# Board_scheme.net
KiCad netlist of a schematic drawn in EasyEDA
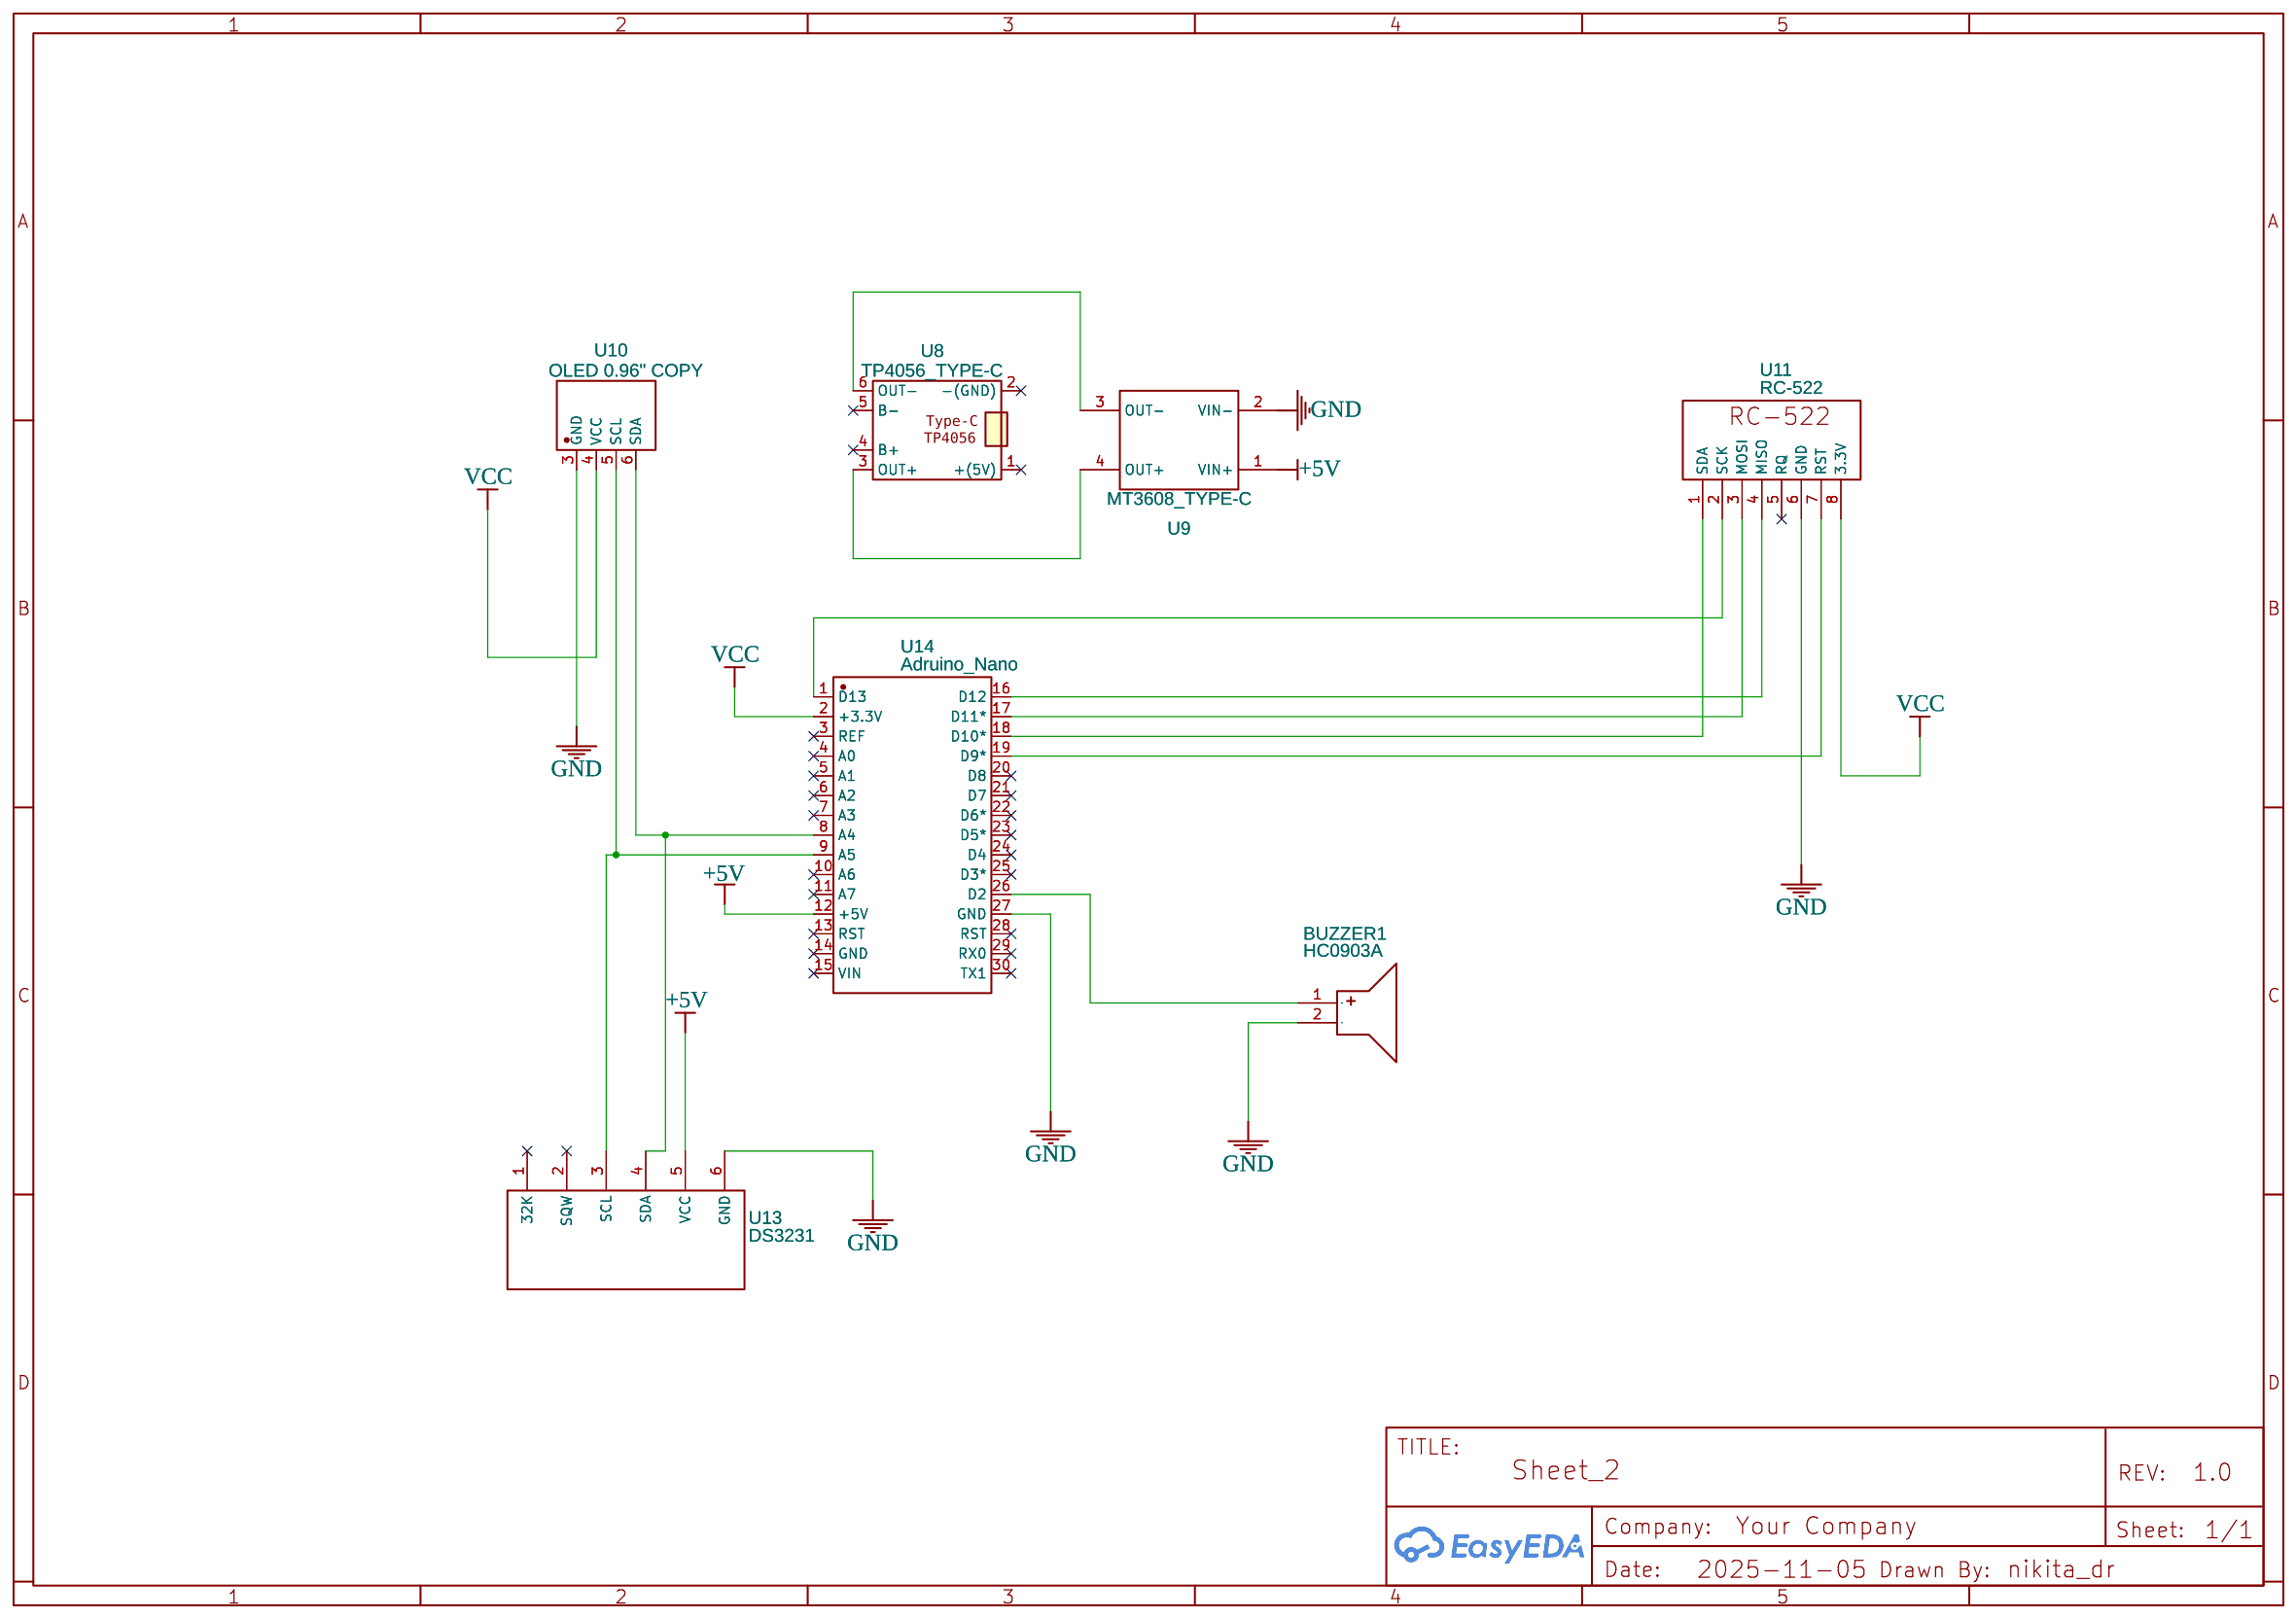
[diagram p0: schematic sheet]

(export (version "E")
  (design (tool "Eeschema 10.0.6"))
  (components
    (comp (ref "BUZZER1")
      (value "HC0903A")
      (fields (field (name "Manufacturer") "INGHAi"))
      (libsource (lib "") (part "HC0903A"))
    )
    (comp (ref "U8") (value "TP4056_TYPE-C") (libsource (lib "") (part "TP4056_TYPE-C")))
    (comp (ref "U9")
      (value "MT3608_TYPE-C")
      (fields (field (name "Manufacturer") "Simple Robot Store"))
      (libsource (lib "") (part "MT3608_TYPE-C"))
    )
    (comp (ref "U10")
      (value "OLED 0.96\" COPY")
      (fields
        (field (name "Manufacturer Part") "ZJY096S0700BG01蓝色")
        (field (name "Manufacturer") "AZDelivery")
      )
      (libsource (lib "") (part "OLED 0.96{dblquote} COPY"))
    )
    (comp (ref "U11") (value "RC-522") (libsource (lib "") (part "RC-522")))
    (comp (ref "U13")
      (value "DS3231")
      (fields (field (name "Manufacturer Part") "New SchematicLib"))
      (libsource (lib "") (part "DS3231"))
    )
    (comp (ref "U14") (value "Adruino_Nano") (libsource (lib "") (part "Adruino_Nano")))
  )
  (nets
    (net (code "1") (name "+5V") (class "Default")
      (node (ref "U13") (pin "5") (pinfunction "VCC_5") (pintype "unspecified"))
      (node (ref "U14") (pin "12") (pinfunction "+5V_12") (pintype "unspecified"))
      (node (ref "U9") (pin "1") (pinfunction "VIN+_1") (pintype "unspecified"))
    )
    (net (code "2") (name "GND") (class "Default")
      (node (ref "BUZZER1") (pin "2") (pinfunction "-_2") (pintype "unspecified"))
      (node (ref "U10") (pin "3") (pinfunction "GND_3") (pintype "unspecified"))
      (node (ref "U11") (pin "6") (pinfunction "GND_6") (pintype "unspecified"))
      (node (ref "U13") (pin "6") (pinfunction "GND_6") (pintype "unspecified"))
      (node (ref "U14") (pin "27") (pinfunction "GND_27") (pintype "unspecified"))
      (node (ref "U9") (pin "2") (pinfunction "VIN-_2") (pintype "unspecified"))
    )
    (net (code "3") (name "Net-(BUZZER1-+)") (class "Default")
      (node (ref "BUZZER1") (pin "1") (pinfunction "+_1") (pintype "unspecified"))
      (node (ref "U14") (pin "26") (pinfunction "D2_26") (pintype "unspecified"))
    )
    (net (code "4") (name "Net-(U8-OUT+)") (class "Default")
      (node (ref "U8") (pin "3") (pinfunction "OUT+_3") (pintype "unspecified"))
      (node (ref "U9") (pin "4") (pinfunction "OUT+_4") (pintype "unspecified"))
    )
    (net (code "5") (name "Net-(U8-OUT-)") (class "Default")
      (node (ref "U8") (pin "6") (pinfunction "OUT-_6") (pintype "unspecified"))
      (node (ref "U9") (pin "3") (pinfunction "OUT-_3") (pintype "unspecified"))
    )
    (net (code "6") (name "Net-(U10-SCL)") (class "Default")
      (node (ref "U10") (pin "5") (pinfunction "SCL_5") (pintype "unspecified"))
      (node (ref "U13") (pin "3") (pinfunction "SCL_3") (pintype "unspecified"))
      (node (ref "U14") (pin "9") (pinfunction "A5_9") (pintype "unspecified"))
    )
    (net (code "7") (name "Net-(U10-SDA)") (class "Default")
      (node (ref "U10") (pin "6") (pinfunction "SDA_6") (pintype "unspecified"))
      (node (ref "U13") (pin "4") (pinfunction "SDA_4") (pintype "unspecified"))
      (node (ref "U14") (pin "8") (pinfunction "A4_8") (pintype "unspecified"))
    )
    (net (code "8") (name "Net-(U11-MISO)") (class "Default")
      (node (ref "U11") (pin "4") (pinfunction "MISO_4") (pintype "unspecified"))
      (node (ref "U14") (pin "16") (pinfunction "D12_16") (pintype "unspecified"))
    )
    (net (code "9") (name "Net-(U11-MOSI)") (class "Default")
      (node (ref "U11") (pin "3") (pinfunction "MOSI_3") (pintype "unspecified"))
      (node (ref "U14") (pin "17") (pinfunction "D11*_17") (pintype "unspecified"))
    )
    (net (code "10") (name "Net-(U11-RST)") (class "Default")
      (node (ref "U11") (pin "7") (pinfunction "RST_7") (pintype "unspecified"))
      (node (ref "U14") (pin "19") (pinfunction "D9*_19") (pintype "unspecified"))
    )
    (net (code "11") (name "Net-(U11-SCK)") (class "Default")
      (node (ref "U11") (pin "2") (pinfunction "SCK_2") (pintype "unspecified"))
      (node (ref "U14") (pin "1") (pinfunction "D13_1") (pintype "unspecified"))
    )
    (net (code "12") (name "Net-(U11-SDA)") (class "Default")
      (node (ref "U11") (pin "1") (pinfunction "SDA_1") (pintype "unspecified"))
      (node (ref "U14") (pin "18") (pinfunction "D10*_18") (pintype "unspecified"))
    )
    (net (code "13") (name "VCC") (class "Default")
      (node (ref "U10") (pin "4") (pinfunction "VCC_4") (pintype "unspecified"))
      (node (ref "U11") (pin "8") (pinfunction "3.3V_8") (pintype "unspecified"))
      (node (ref "U14") (pin "2") (pinfunction "+3.3V_2") (pintype "unspecified"))
    )
    (net (code "14") (name "unconnected-(U8-+(5V)-Pad1)") (class "Default")
      (node (ref "U8") (pin "1") (pinfunction "+(5V)_1") (pintype "unspecified+no_connect"))
    )
    (net (code "15") (name "unconnected-(U8--(GND)-Pad2)") (class "Default")
      (node (ref "U8") (pin "2") (pinfunction "-(GND)_2") (pintype "unspecified+no_connect"))
    )
    (net (code "16") (name "unconnected-(U8-B+-Pad4)") (class "Default")
      (node (ref "U8") (pin "4") (pinfunction "B+_4") (pintype "unspecified+no_connect"))
    )
    (net (code "17") (name "unconnected-(U8-B--Pad5)") (class "Default")
      (node (ref "U8") (pin "5") (pinfunction "B-_5") (pintype "unspecified+no_connect"))
    )
    (net (code "18") (name "unconnected-(U11-RQ-Pad5)") (class "Default")
      (node (ref "U11") (pin "5") (pinfunction "RQ_5") (pintype "unspecified+no_connect"))
    )
    (net (code "19") (name "unconnected-(U13-32K-Pad1)") (class "Default")
      (node (ref "U13") (pin "1") (pinfunction "32K_1") (pintype "unspecified+no_connect"))
    )
    (net (code "20") (name "unconnected-(U13-SQW-Pad2)") (class "Default")
      (node (ref "U13") (pin "2") (pinfunction "SQW_2") (pintype "unspecified+no_connect"))
    )
    (net (code "21") (name "unconnected-(U14-A0-Pad4)") (class "Default")
      (node (ref "U14") (pin "4") (pinfunction "A0_4") (pintype "unspecified+no_connect"))
    )
    (net (code "22") (name "unconnected-(U14-A1-Pad5)") (class "Default")
      (node (ref "U14") (pin "5") (pinfunction "A1_5") (pintype "unspecified+no_connect"))
    )
    (net (code "23") (name "unconnected-(U14-A2-Pad6)") (class "Default")
      (node (ref "U14") (pin "6") (pinfunction "A2_6") (pintype "unspecified+no_connect"))
    )
    (net (code "24") (name "unconnected-(U14-A3-Pad7)") (class "Default")
      (node (ref "U14") (pin "7") (pinfunction "A3_7") (pintype "unspecified+no_connect"))
    )
    (net (code "25") (name "unconnected-(U14-A6-Pad10)") (class "Default")
      (node (ref "U14") (pin "10") (pinfunction "A6_10") (pintype "unspecified+no_connect"))
    )
    (net (code "26") (name "unconnected-(U14-A7-Pad11)") (class "Default")
      (node (ref "U14") (pin "11") (pinfunction "A7_11") (pintype "unspecified+no_connect"))
    )
    (net (code "27") (name "unconnected-(U14-D3*-Pad25)") (class "Default")
      (node (ref "U14") (pin "25") (pinfunction "D3*_25") (pintype "unspecified+no_connect"))
    )
    (net (code "28") (name "unconnected-(U14-D4-Pad24)") (class "Default")
      (node (ref "U14") (pin "24") (pinfunction "D4_24") (pintype "unspecified+no_connect"))
    )
    (net (code "29") (name "unconnected-(U14-D5*-Pad23)") (class "Default")
      (node (ref "U14") (pin "23") (pinfunction "D5*_23") (pintype "unspecified+no_connect"))
    )
    (net (code "30") (name "unconnected-(U14-D6*-Pad22)") (class "Default")
      (node (ref "U14") (pin "22") (pinfunction "D6*_22") (pintype "unspecified+no_connect"))
    )
    (net (code "31") (name "unconnected-(U14-D7-Pad21)") (class "Default")
      (node (ref "U14") (pin "21") (pinfunction "D7_21") (pintype "unspecified+no_connect"))
    )
    (net (code "32") (name "unconnected-(U14-D8-Pad20)") (class "Default")
      (node (ref "U14") (pin "20") (pinfunction "D8_20") (pintype "unspecified+no_connect"))
    )
    (net (code "33") (name "unconnected-(U14-GND-Pad14)") (class "Default")
      (node (ref "U14") (pin "14") (pinfunction "GND_14") (pintype "unspecified+no_connect"))
    )
    (net (code "34") (name "unconnected-(U14-REF-Pad3)") (class "Default")
      (node (ref "U14") (pin "3") (pinfunction "REF_3") (pintype "unspecified+no_connect"))
    )
    (net (code "35") (name "unconnected-(U14-RST-Pad13)") (class "Default")
      (node (ref "U14") (pin "13") (pinfunction "RST_13") (pintype "unspecified+no_connect"))
    )
    (net (code "36") (name "unconnected-(U14-RST-Pad28)") (class "Default")
      (node (ref "U14") (pin "28") (pinfunction "RST_28") (pintype "unspecified+no_connect"))
    )
    (net (code "37") (name "unconnected-(U14-RX0-Pad29)") (class "Default")
      (node (ref "U14") (pin "29") (pinfunction "RX0_29") (pintype "unspecified+no_connect"))
    )
    (net (code "38") (name "unconnected-(U14-TX1-Pad30)") (class "Default")
      (node (ref "U14") (pin "30") (pinfunction "TX1_30") (pintype "unspecified+no_connect"))
    )
    (net (code "39") (name "unconnected-(U14-VIN-Pad15)") (class "Default")
      (node (ref "U14") (pin "15") (pinfunction "VIN_15") (pintype "unspecified+no_connect"))
    )
  )
)
